# Ethernet.net
KiCad netlist of a schematic drawn in Altium Designer
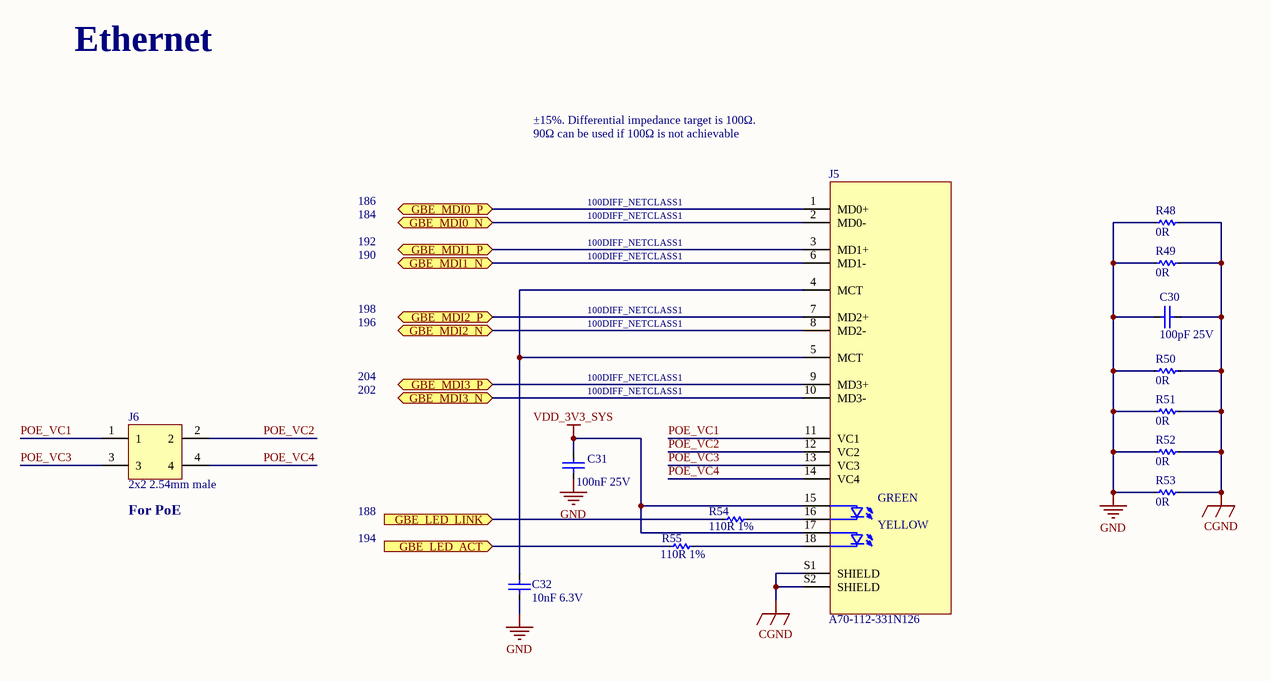
[diagram p0: Ethernet.SchDoc]

(export (version "E")
  (design (tool "Eeschema 10.0.6"))
  (components
    (comp (ref "C30")
      (value "100pF 25V")
      (footprint "C0402")
      (description "Cap Ceramic 100pF 25V C0G 5% SMD 0402 125C Paper T/R")
      (fields
        (field (name "MANUFACTURER") "KEMET")
        (field (name "MANUFACTURER PART NUMBER") "C0402C101J3GACTU")
      )
      (libsource (lib "GM_Altium_Library") (part "C0402C101J3GACTU"))
    )
    (comp (ref "C31")
      (value "100nF 25V")
      (footprint "C0402")
      (description "CAP CER 0.1UF 25V X5R 0402 / High Value Multilayer Ceramic Capacitors (High dielectric type)")
      (fields
        (field (name "MANUFACTURER") "Taiyo Yuden")
        (field (name "MANUFACTURER PART NUMBER") "TMK105BJ104KV-F")
      )
      (libsource (lib "GM_Altium_Library") (part "TMK105BJ104KV-F"))
    )
    (comp (ref "C32")
      (value "10nF 6.3V")
      (footprint "C0402")
      (description "0402 10 nF 6.3V ±10% Tolerance X5R SMT Multilayer Ceramic Capacitor")
      (fields
        (field (name "MANUFACTURER") "Murata")
        (field (name "MANUFACTURER PART NUMBER") "GRM155R60J103KA01D")
      )
      (libsource (lib "GM_Altium_Library") (part "GRM155R60J103KA01D"))
    )
    (comp (ref "J5")
      (value "A70-112-331N126")
      (footprint "A70-112-331N126")
      (description "RJ45 MAGNETIC JACK WITH LED")
      (libsource (lib "GM_Altium_Library") (part "A70-112-331N126"))
    )
    (comp (ref "J6")
      (value "2x2 2.54mm male")
      (footprint "PEC02DABN")
      (description "Conn Header Vert 4POS 2.54MM")
      (fields (field (name "MANUFACTURER") "Sullins") (field (name "MANUFACTURER PART NUMBER") "PEC02DABN"))
      (libsource (lib "GM_Altium_Library") (part "PEC02DABN"))
    )
    (comp (ref "R48")
      (value "0R")
      (footprint "R0603")
      (description "RES SMD 0 OHM JUMPER 1/10W 0603")
      (fields
        (field (name "MANUFACTURER") "Bourns")
        (field (name "MANUFACTURER PART NUMBER") "CR0603-J/-000ELF")
      )
      (libsource (lib "GM_Altium_Library") (part "CR0603-J/-000ELF"))
    )
    (comp (ref "R49")
      (value "0R")
      (footprint "R0603")
      (description "RES SMD 0 OHM JUMPER 1/10W 0603")
      (fields
        (field (name "MANUFACTURER") "Bourns")
        (field (name "MANUFACTURER PART NUMBER") "CR0603-J/-000ELF")
      )
      (libsource (lib "GM_Altium_Library") (part "CR0603-J/-000ELF"))
    )
    (comp (ref "R50")
      (value "0R")
      (footprint "R0603")
      (description "RES SMD 0 OHM JUMPER 1/10W 0603")
      (fields
        (field (name "MANUFACTURER") "Bourns")
        (field (name "MANUFACTURER PART NUMBER") "CR0603-J/-000ELF")
      )
      (libsource (lib "GM_Altium_Library") (part "CR0603-J/-000ELF"))
    )
    (comp (ref "R51")
      (value "0R")
      (footprint "R0603")
      (description "RES SMD 0 OHM JUMPER 1/10W 0603")
      (fields
        (field (name "MANUFACTURER") "Bourns")
        (field (name "MANUFACTURER PART NUMBER") "CR0603-J/-000ELF")
      )
      (libsource (lib "GM_Altium_Library") (part "CR0603-J/-000ELF"))
    )
    (comp (ref "R52")
      (value "0R")
      (footprint "R0603")
      (description "RES SMD 0 OHM JUMPER 1/10W 0603")
      (fields
        (field (name "MANUFACTURER") "Bourns")
        (field (name "MANUFACTURER PART NUMBER") "CR0603-J/-000ELF")
      )
      (libsource (lib "GM_Altium_Library") (part "CR0603-J/-000ELF"))
    )
    (comp (ref "R53")
      (value "0R")
      (footprint "R0603")
      (description "RES SMD 0 OHM JUMPER 1/10W 0603")
      (fields
        (field (name "MANUFACTURER") "Bourns")
        (field (name "MANUFACTURER PART NUMBER") "CR0603-J/-000ELF")
      )
      (libsource (lib "GM_Altium_Library") (part "CR0603-J/-000ELF"))
    )
    (comp (ref "R54")
      (value "110R 1%")
      (footprint "R0402")
      (description "High Precision-High Stability Chip Resistor Thin Film 0402 110Ohm 1% Paper T/R")
      (fields
        (field (name "MANUFACTURER") "Yageo")
        (field (name "MANUFACTURER PART NUMBER") "RT0402FRE07110RL")
      )
      (libsource (lib "GM_Altium_Library") (part "RT0402FRE07110RL"))
    )
    (comp (ref "R55")
      (value "110R 1%")
      (footprint "R0402")
      (description "High Precision-High Stability Chip Resistor Thin Film 0402 110Ohm 1% Paper T/R")
      (fields
        (field (name "MANUFACTURER") "Yageo")
        (field (name "MANUFACTURER PART NUMBER") "RT0402FRE07110RL")
      )
      (libsource (lib "GM_Altium_Library") (part "RT0402FRE07110RL"))
    )
  )
  (nets
    (net (code "1") (name "/GBE_LED_ACT") (class "Default")
      (node (ref "R55") (pin "1") (pinfunction "1_1") (pintype "passive"))
    )
    (net (code "2") (name "/GBE_LED_LINK") (class "Default")
      (node (ref "R54") (pin "1") (pinfunction "1_1") (pintype "passive"))
    )
    (net (code "3") (name "/GBE_MDI0_N") (class "Default")
      (node (ref "J5") (pin "2") (pinfunction "MD0-_2") (pintype "passive"))
    )
    (net (code "4") (name "/GBE_MDI0_P") (class "Default")
      (node (ref "J5") (pin "1") (pinfunction "MD0+_1") (pintype "passive"))
    )
    (net (code "5") (name "/GBE_MDI1_N") (class "Default")
      (node (ref "J5") (pin "6") (pinfunction "MD1-_6") (pintype "passive"))
    )
    (net (code "6") (name "/GBE_MDI1_P") (class "Default")
      (node (ref "J5") (pin "3") (pinfunction "MD1+_3") (pintype "passive"))
    )
    (net (code "7") (name "/GBE_MDI2_N") (class "Default")
      (node (ref "J5") (pin "8") (pinfunction "MD2-_8") (pintype "passive"))
    )
    (net (code "8") (name "/GBE_MDI2_P") (class "Default")
      (node (ref "J5") (pin "7") (pinfunction "MD2+_7") (pintype "passive"))
    )
    (net (code "9") (name "/GBE_MDI3_N") (class "Default")
      (node (ref "J5") (pin "10") (pinfunction "MD3-_10") (pintype "passive"))
    )
    (net (code "10") (name "/GBE_MDI3_P") (class "Default")
      (node (ref "J5") (pin "9") (pinfunction "MD3+_9") (pintype "passive"))
    )
    (net (code "11") (name "/POE_VC1") (class "Default")
      (node (ref "J5") (pin "11") (pinfunction "VC1_11") (pintype "passive"))
      (node (ref "J6") (pin "1") (pinfunction "1_1") (pintype "passive"))
    )
    (net (code "12") (name "/POE_VC2") (class "Default")
      (node (ref "J5") (pin "12") (pinfunction "VC2_12") (pintype "passive"))
      (node (ref "J6") (pin "2") (pinfunction "2_2") (pintype "passive"))
    )
    (net (code "13") (name "/POE_VC3") (class "Default")
      (node (ref "J5") (pin "13") (pinfunction "VC3_13") (pintype "passive"))
      (node (ref "J6") (pin "3") (pinfunction "3_3") (pintype "passive"))
    )
    (net (code "14") (name "/POE_VC4") (class "Default")
      (node (ref "J5") (pin "14") (pinfunction "VC4_14") (pintype "passive"))
      (node (ref "J6") (pin "4") (pinfunction "4_4") (pintype "passive"))
    )
    (net (code "15") (name "CGND") (class "Default")
      (node (ref "C30") (pin "2") (pinfunction "2_2") (pintype "passive"))
      (node (ref "J5") (pin "S1") (pinfunction "SHIELD_S1") (pintype "passive"))
      (node (ref "J5") (pin "S2") (pinfunction "SHIELD_S2") (pintype "passive"))
      (node (ref "R48") (pin "2") (pinfunction "2_2") (pintype "passive"))
      (node (ref "R49") (pin "2") (pinfunction "2_2") (pintype "passive"))
      (node (ref "R50") (pin "2") (pinfunction "2_2") (pintype "passive"))
      (node (ref "R51") (pin "2") (pinfunction "2_2") (pintype "passive"))
      (node (ref "R52") (pin "2") (pinfunction "2_2") (pintype "passive"))
      (node (ref "R53") (pin "2") (pinfunction "2_2") (pintype "passive"))
    )
    (net (code "16") (name "GND") (class "Default")
      (node (ref "C30") (pin "1") (pinfunction "1_1") (pintype "passive"))
      (node (ref "C31") (pin "1") (pinfunction "1_1") (pintype "passive"))
      (node (ref "C32") (pin "1") (pinfunction "1_1") (pintype "passive"))
      (node (ref "R48") (pin "1") (pinfunction "1_1") (pintype "passive"))
      (node (ref "R49") (pin "1") (pinfunction "1_1") (pintype "passive"))
      (node (ref "R50") (pin "1") (pinfunction "1_1") (pintype "passive"))
      (node (ref "R51") (pin "1") (pinfunction "1_1") (pintype "passive"))
      (node (ref "R52") (pin "1") (pinfunction "1_1") (pintype "passive"))
      (node (ref "R53") (pin "1") (pinfunction "1_1") (pintype "passive"))
    )
    (net (code "17") (name "Net-(C32-Pad2)") (class "Default")
      (node (ref "C32") (pin "2") (pinfunction "2_2") (pintype "passive"))
      (node (ref "J5") (pin "4") (pinfunction "MCT_4") (pintype "passive"))
      (node (ref "J5") (pin "5") (pinfunction "MCT_5") (pintype "passive"))
    )
    (net (code "18") (name "Net-(J5-G_K)") (class "Default")
      (node (ref "J5") (pin "16") (pinfunction "G_K_16") (pintype "passive"))
      (node (ref "R54") (pin "2") (pinfunction "2_2") (pintype "passive"))
    )
    (net (code "19") (name "Net-(J5-Y_K)") (class "Default")
      (node (ref "J5") (pin "18") (pinfunction "Y_K_18") (pintype "passive"))
      (node (ref "R55") (pin "2") (pinfunction "2_2") (pintype "passive"))
    )
    (net (code "20") (name "VDD_3V3_SYS") (class "Default")
      (node (ref "C31") (pin "2") (pinfunction "2_2") (pintype "passive"))
      (node (ref "J5") (pin "15") (pinfunction "G_A_15") (pintype "passive"))
      (node (ref "J5") (pin "17") (pinfunction "Y_A_17") (pintype "passive"))
    )
  )
)
